# bristol_longshot.net
KiCad netlist of a schematic drawn in EAGLE
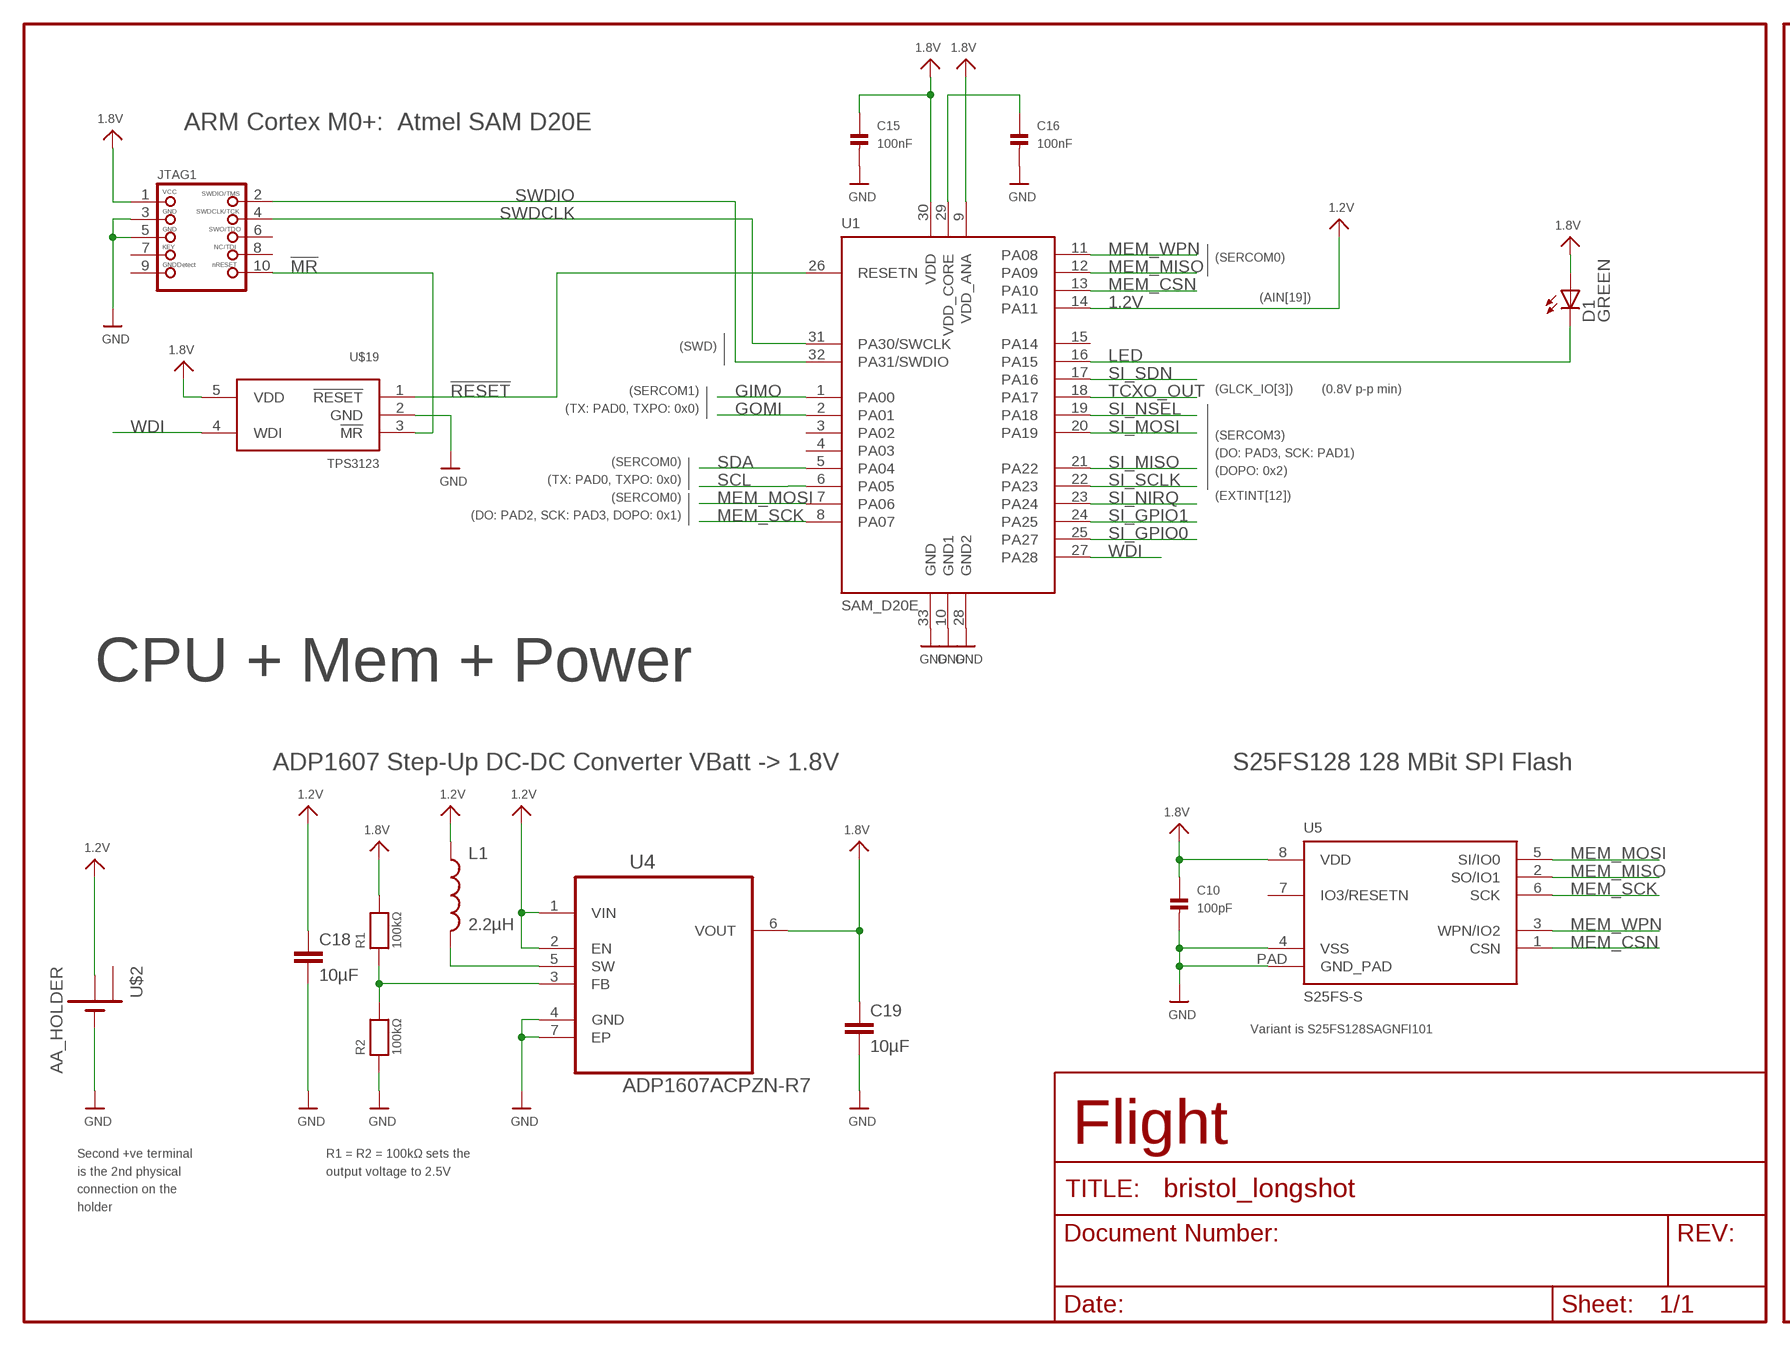
[diagram p0: schematic, sheet 1, part 1 of 2]
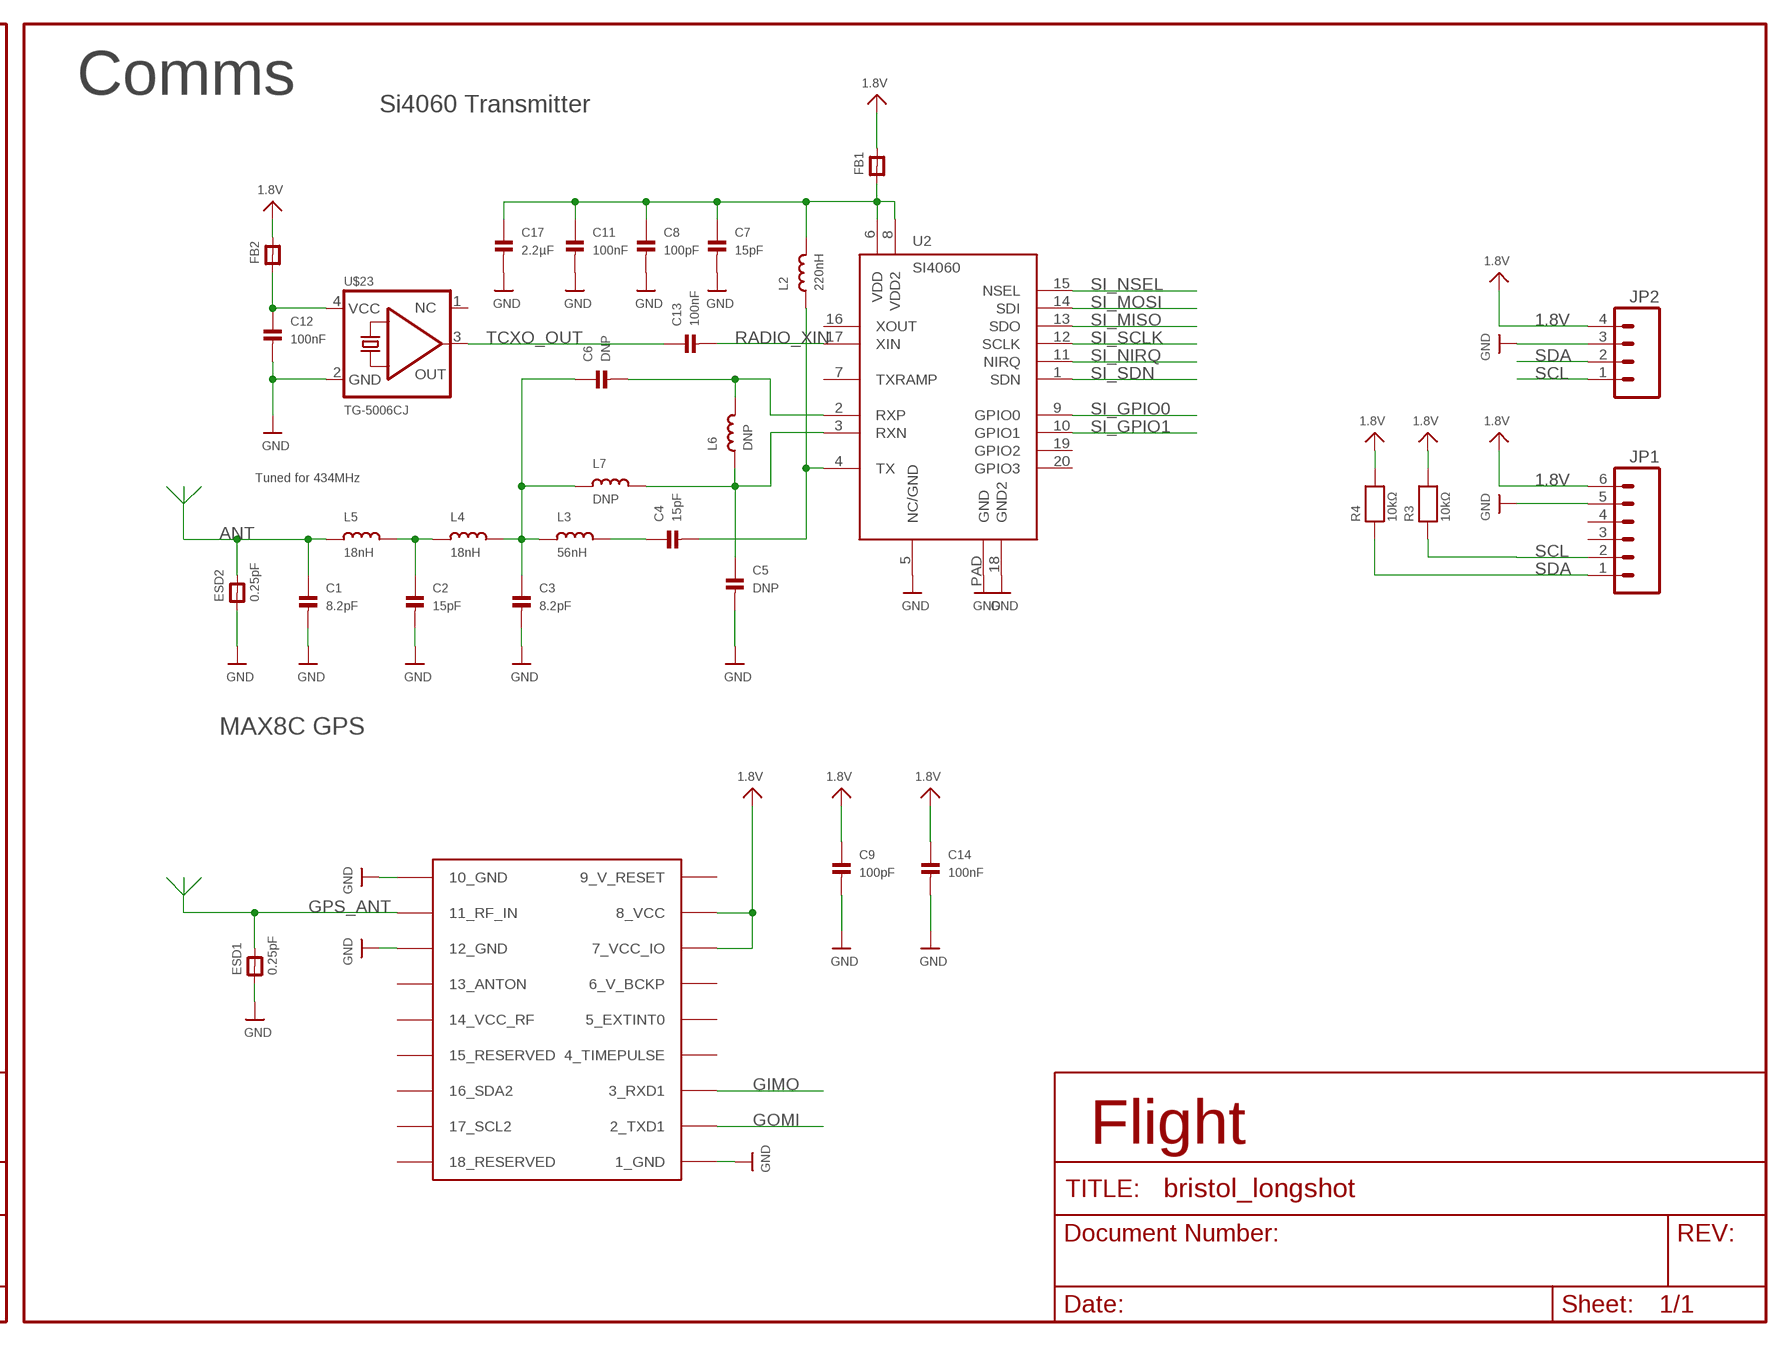
[diagram p1: schematic, sheet 1, part 2 of 2]

(export (version "E")
  (design (tool "Eeschema 10.0.6"))
  (components
    (comp (ref "C1")
      (value "8.2pF")
      (footprint "eagle-import:_0402")
      (libsource (lib "eagle-import") (part "CAP_CERAMIC_0402"))
    )
    (comp (ref "C2")
      (value "15pF")
      (footprint "eagle-import:_0402")
      (libsource (lib "eagle-import") (part "CAP_CERAMIC_0402"))
    )
    (comp (ref "C3")
      (value "8.2pF")
      (footprint "eagle-import:_0402")
      (libsource (lib "eagle-import") (part "CAP_CERAMIC_0402"))
    )
    (comp (ref "C4")
      (value "15pF")
      (footprint "eagle-import:_0402")
      (libsource (lib "eagle-import") (part "CAP_CERAMIC_0402"))
    )
    (comp (ref "C5")
      (value "DNP")
      (footprint "eagle-import:_0402")
      (libsource (lib "eagle-import") (part "CAP_CERAMIC_0402"))
    )
    (comp (ref "C6")
      (value "DNP")
      (footprint "eagle-import:_0402")
      (libsource (lib "eagle-import") (part "CAP_CERAMIC_0402"))
    )
    (comp (ref "C7")
      (value "15pF")
      (footprint "eagle-import:_0402")
      (libsource (lib "eagle-import") (part "CAP_CERAMIC_0402"))
    )
    (comp (ref "C8")
      (value "100pF")
      (footprint "eagle-import:_0402")
      (libsource (lib "eagle-import") (part "CAP_CERAMIC_0402"))
    )
    (comp (ref "C9")
      (value "100pF")
      (footprint "eagle-import:_0402")
      (libsource (lib "eagle-import") (part "CAP_CERAMIC_0402"))
    )
    (comp (ref "C10")
      (value "100pF")
      (footprint "eagle-import:_0402")
      (libsource (lib "eagle-import") (part "CAP_CERAMIC_0402"))
    )
    (comp (ref "C11")
      (value "100nF")
      (footprint "eagle-import:_0402")
      (libsource (lib "eagle-import") (part "CAP_CERAMIC_0402"))
    )
    (comp (ref "C12")
      (value "100nF")
      (footprint "eagle-import:_0402")
      (libsource (lib "eagle-import") (part "CAP_CERAMIC_0402"))
    )
    (comp (ref "C13")
      (value "100nF")
      (footprint "eagle-import:_0402")
      (libsource (lib "eagle-import") (part "CAP_CERAMIC_0402"))
    )
    (comp (ref "C14")
      (value "100nF")
      (footprint "eagle-import:_0402")
      (libsource (lib "eagle-import") (part "CAP_CERAMIC_0402"))
    )
    (comp (ref "C15")
      (value "100nF")
      (footprint "eagle-import:_0402")
      (libsource (lib "eagle-import") (part "CAP_CERAMIC_0402"))
    )
    (comp (ref "C16")
      (value "100nF")
      (footprint "eagle-import:_0402")
      (libsource (lib "eagle-import") (part "CAP_CERAMIC_0402"))
    )
    (comp (ref "C17")
      (value "2.2µF")
      (footprint "eagle-import:_0402")
      (libsource (lib "eagle-import") (part "CAP_CERAMIC_0402"))
    )
    (comp (ref "C18")
      (value "10µF")
      (footprint "eagle-import:C0603K")
      (libsource (lib "eagle-import") (part "C-EUC0603K"))
    )
    (comp (ref "C19")
      (value "10µF")
      (footprint "eagle-import:C0603K")
      (libsource (lib "eagle-import") (part "C-EUC0603K"))
    )
    (comp (ref "D1")
      (value "GREEN")
      (footprint "eagle-import:CHIPLED_0603")
      (libsource (lib "eagle-import") (part "LEDCHIPLED_0603"))
    )
    (comp (ref "ESD1")
      (value "0.25pF")
      (footprint "eagle-import:_0603MP")
      (libsource (lib "eagle-import") (part "FERRITE_0603MP"))
    )
    (comp (ref "ESD2")
      (value "0.25pF")
      (footprint "eagle-import:_0603MP")
      (libsource (lib "eagle-import") (part "FERRITE_0603MP"))
    )
    (comp (ref "FB1")
      (value "FERRITE_0402")
      (footprint "eagle-import:_0402")
      (libsource (lib "eagle-import") (part "FERRITE_0402"))
    )
    (comp (ref "FB2")
      (value "FERRITE_0402")
      (footprint "eagle-import:_0402")
      (libsource (lib "eagle-import") (part "FERRITE_0402"))
    )
    (comp (ref "JP1")
      (value "M06LOCK")
      (footprint "eagle-import:1X06_LOCK")
      (libsource (lib "eagle-import") (part "M06LOCK"))
    )
    (comp (ref "JP2")
      (value "M04LOCK")
      (footprint "eagle-import:1X04_LOCK")
      (libsource (lib "eagle-import") (part "M04LOCK"))
    )
    (comp (ref "JTAG1")
      (value "JTAG-CORTEXM3SMT")
      (footprint "eagle-import:2X05_1.27MM_SMT")
      (libsource (lib "eagle-import") (part "JTAG-CORTEXM3SMT"))
    )
    (comp (ref "L1")
      (value "2.2µH")
      (footprint "eagle-import:1007")
      (libsource (lib "eagle-import") (part "INDUCTOR1007"))
    )
    (comp (ref "L2")
      (value "220nH")
      (footprint "eagle-import:_0402")
      (libsource (lib "eagle-import") (part "INDUCTOR_0402"))
    )
    (comp (ref "L3")
      (value "56nH")
      (footprint "eagle-import:_0402")
      (libsource (lib "eagle-import") (part "INDUCTOR_0402"))
    )
    (comp (ref "L4")
      (value "18nH")
      (footprint "eagle-import:_0402")
      (libsource (lib "eagle-import") (part "INDUCTOR_0402"))
    )
    (comp (ref "L5")
      (value "18nH")
      (footprint "eagle-import:_0402")
      (libsource (lib "eagle-import") (part "INDUCTOR_0402"))
    )
    (comp (ref "L6")
      (value "DNP")
      (footprint "eagle-import:_0402")
      (libsource (lib "eagle-import") (part "INDUCTOR_0402"))
    )
    (comp (ref "L7")
      (value "DNP")
      (footprint "eagle-import:_0402")
      (libsource (lib "eagle-import") (part "INDUCTOR_0402"))
    )
    (comp (ref "R1")
      (value "100kΩ")
      (footprint "eagle-import:_0402")
      (libsource (lib "eagle-import") (part "RESISTOR_0402"))
    )
    (comp (ref "R2")
      (value "100kΩ")
      (footprint "eagle-import:_0402")
      (libsource (lib "eagle-import") (part "RESISTOR_0402"))
    )
    (comp (ref "R3")
      (value "10kΩ")
      (footprint "eagle-import:_0402")
      (libsource (lib "eagle-import") (part "RESISTOR_0402"))
    )
    (comp (ref "R4")
      (value "10kΩ")
      (footprint "eagle-import:_0402")
      (libsource (lib "eagle-import") (part "RESISTOR_0402"))
    )
    (comp (ref "U$2")
      (value "AA_HOLDER")
      (footprint "eagle-import:AA")
      (libsource (lib "eagle-import") (part "AA_HOLDER"))
    )
    (comp (ref "U$19")
      (value "TPS3123")
      (footprint "eagle-import:SOT23-5")
      (libsource (lib "eagle-import") (part "TPS3123"))
    )
    (comp (ref "U$23")
      (value "TG-5006CJ")
      (footprint "eagle-import:TC-5006CJ")
      (libsource (lib "eagle-import") (part "TG-5006CJ"))
    )
    (comp (ref "U$48")
      (value "UBLOX_MAX")
      (footprint "eagle-import:UBLOX_MAX")
      (libsource (lib "eagle-import") (part "UBLOX_MAX"))
    )
    (comp (ref "U1")
      (value "SAM_D20E")
      (footprint "eagle-import:QFN32_5MM")
      (libsource (lib "eagle-import") (part "SAM_D20E"))
    )
    (comp (ref "U2")
      (value "SI4060")
      (footprint "eagle-import:QFN20")
      (libsource (lib "eagle-import") (part "SI4060"))
    )
    (comp (ref "U4")
      (value "ADP1607ACPZN-R7")
      (footprint "eagle-import:DFN200X200X60-7N")
      (libsource (lib "eagle-import") (part "ADP1607ACPZN-R7"))
    )
    (comp (ref "U5")
      (value "S25FS-S")
      (footprint "eagle-import:WSON8")
      (libsource (lib "eagle-import") (part "S25FS-S"))
    )
  )
  (nets
    (net (code "1") (name "/+2") (class "Default")
      (node (ref "U$2") (pin "+1") (pinfunction "+2_+1") (pintype "power_in"))
    )
    (net (code "2") (name "/9_V_RESET") (class "Default")
      (node (ref "U$48") (pin "9_V_RESET") (pinfunction "9_V_RESET_9_V_RESET") (pintype "power_in"))
    )
    (net (code "3") (name "/ANT") (class "Default")
      (node (ref "C1") (pin "1") (pinfunction "P$1_1") (pintype "passive"))
      (node (ref "ESD2") (pin "2") (pinfunction "P$2_2") (pintype "passive"))
      (node (ref "L5") (pin "1") (pinfunction "1_1") (pintype "passive"))
    )
    (net (code "4") (name "/GIMO") (class "Default")
      (node (ref "U$48") (pin "3_RXD1") (pinfunction "3_RXD1_3_RXD1") (pintype "bidirectional"))
      (node (ref "U1") (pin "1") (pinfunction "PA00_1") (pintype "bidirectional"))
    )
    (net (code "5") (name "/GOMI") (class "Default")
      (node (ref "U$48") (pin "2_TXD1") (pinfunction "2_TXD1_2_TXD1") (pintype "bidirectional"))
      (node (ref "U1") (pin "2") (pinfunction "PA01_2") (pintype "bidirectional"))
    )
    (net (code "6") (name "/GPS_ANT") (class "Default")
      (node (ref "ESD1") (pin "2") (pinfunction "P$2_2") (pintype "passive"))
      (node (ref "U$48") (pin "11_RF_IN") (pinfunction "11_RF_IN_11_RF_IN") (pintype "bidirectional"))
    )
    (net (code "7") (name "/LED") (class "Default")
      (node (ref "D1") (pin "C") (pinfunction "C_C") (pintype "passive"))
      (node (ref "U1") (pin "16") (pinfunction "PA15_16") (pintype "bidirectional"))
    )
    (net (code "8") (name "/MEM_CSN") (class "Default")
      (node (ref "U1") (pin "13") (pinfunction "PA10_13") (pintype "bidirectional"))
      (node (ref "U5") (pin "1") (pinfunction "CSN_1") (pintype "input"))
    )
    (net (code "9") (name "/MEM_MISO") (class "Default")
      (node (ref "U1") (pin "12") (pinfunction "PA09_12") (pintype "bidirectional"))
      (node (ref "U5") (pin "2") (pinfunction "SO/IO1_2") (pintype "output"))
    )
    (net (code "10") (name "/MEM_MOSI") (class "Default")
      (node (ref "U1") (pin "7") (pinfunction "PA06_7") (pintype "bidirectional"))
      (node (ref "U5") (pin "5") (pinfunction "SI/IO0_5") (pintype "bidirectional"))
    )
    (net (code "11") (name "/MEM_SCK") (class "Default")
      (node (ref "U1") (pin "8") (pinfunction "PA07_8") (pintype "bidirectional"))
      (node (ref "U5") (pin "6") (pinfunction "SCK_6") (pintype "input"))
    )
    (net (code "12") (name "/MEM_WPN") (class "Default")
      (node (ref "U1") (pin "11") (pinfunction "PA08_11") (pintype "bidirectional"))
      (node (ref "U5") (pin "3") (pinfunction "WPN/IO2_3") (pintype "output"))
    )
    (net (code "13") (name "/RADIO_XIN") (class "Default")
      (node (ref "C13") (pin "2") (pinfunction "P$2_2") (pintype "passive"))
      (node (ref "U2") (pin "17") (pinfunction "XIN_17") (pintype "input"))
    )
    (net (code "14") (name "/SCL") (class "Default")
      (node (ref "JP1") (pin "2") (pinfunction "2_2") (pintype "passive"))
      (node (ref "JP2") (pin "1") (pinfunction "1_1") (pintype "passive"))
      (node (ref "R3") (pin "1") (pinfunction "1_1") (pintype "passive"))
      (node (ref "U1") (pin "6") (pinfunction "PA05_6") (pintype "bidirectional"))
    )
    (net (code "15") (name "/SDA") (class "Default")
      (node (ref "JP1") (pin "1") (pinfunction "1_1") (pintype "passive"))
      (node (ref "JP2") (pin "2") (pinfunction "2_2") (pintype "passive"))
      (node (ref "R4") (pin "1") (pinfunction "1_1") (pintype "passive"))
      (node (ref "U1") (pin "5") (pinfunction "PA04_5") (pintype "bidirectional"))
    )
    (net (code "16") (name "/SI_GPIO0") (class "Default")
      (node (ref "U1") (pin "25") (pinfunction "PA27_25") (pintype "bidirectional"))
      (node (ref "U2") (pin "9") (pinfunction "GPIO0_9") (pintype "bidirectional"))
    )
    (net (code "17") (name "/SI_GPIO1") (class "Default")
      (node (ref "U1") (pin "24") (pinfunction "PA25_24") (pintype "bidirectional"))
      (node (ref "U2") (pin "10") (pinfunction "GPIO1_10") (pintype "bidirectional"))
    )
    (net (code "18") (name "/SI_MISO") (class "Default")
      (node (ref "U1") (pin "21") (pinfunction "PA22_21") (pintype "bidirectional"))
      (node (ref "U2") (pin "13") (pinfunction "SDO_13") (pintype "output"))
    )
    (net (code "19") (name "/SI_MOSI") (class "Default")
      (node (ref "U1") (pin "20") (pinfunction "PA19_20") (pintype "bidirectional"))
      (node (ref "U2") (pin "14") (pinfunction "SDI_14") (pintype "bidirectional"))
    )
    (net (code "20") (name "/SI_NIRQ") (class "Default")
      (node (ref "U1") (pin "23") (pinfunction "PA24_23") (pintype "bidirectional"))
      (node (ref "U2") (pin "11") (pinfunction "NIRQ_11") (pintype "output"))
    )
    (net (code "21") (name "/SI_NSEL") (class "Default")
      (node (ref "U1") (pin "19") (pinfunction "PA18_19") (pintype "bidirectional"))
      (node (ref "U2") (pin "15") (pinfunction "NSEL_15") (pintype "input"))
    )
    (net (code "22") (name "/SI_SCLK") (class "Default")
      (node (ref "U1") (pin "22") (pinfunction "PA23_22") (pintype "bidirectional"))
      (node (ref "U2") (pin "12") (pinfunction "SCLK_12") (pintype "input"))
    )
    (net (code "23") (name "/SI_SDN") (class "Default")
      (node (ref "U1") (pin "17") (pinfunction "PA16_17") (pintype "bidirectional"))
      (node (ref "U2") (pin "1") (pinfunction "SDN_1") (pintype "input"))
    )
    (net (code "24") (name "/SWDCLK") (class "Default")
      (node (ref "JTAG1") (pin "4") (pinfunction "4_4") (pintype "passive"))
      (node (ref "U1") (pin "31") (pinfunction "PA30/SWCLK_31") (pintype "bidirectional"))
    )
    (net (code "25") (name "/SWDIO") (class "Default")
      (node (ref "JTAG1") (pin "2") (pinfunction "2_2") (pintype "passive"))
      (node (ref "U1") (pin "32") (pinfunction "PA31/SWDIO_32") (pintype "bidirectional"))
    )
    (net (code "26") (name "/TCXO_OUT") (class "Default")
      (node (ref "C13") (pin "1") (pinfunction "P$1_1") (pintype "passive"))
      (node (ref "U$23") (pin "3") (pinfunction "OUT_3") (pintype "output"))
      (node (ref "U1") (pin "18") (pinfunction "PA17_18") (pintype "bidirectional"))
    )
    (net (code "27") (name "/WDI") (class "Default")
      (node (ref "U$19") (pin "4") (pinfunction "WDI_4") (pintype "bidirectional"))
      (node (ref "U1") (pin "27") (pinfunction "PA28_27") (pintype "bidirectional"))
    )
    (net (code "28") (name "/~{MR}") (class "Default")
      (node (ref "JTAG1") (pin "10") (pinfunction "10_10") (pintype "passive"))
      (node (ref "U$19") (pin "3") (pinfunction "~{MR}_3") (pintype "bidirectional"))
    )
    (net (code "29") (name "/~{RESET}") (class "Default")
      (node (ref "U$19") (pin "1") (pinfunction "~{RESET}_1") (pintype "bidirectional"))
      (node (ref "U1") (pin "26") (pinfunction "RESETN_26") (pintype "input"))
    )
    (net (code "30") (name "1.2V") (class "Default")
      (node (ref "C18") (pin "1") (pinfunction "1_1") (pintype "passive"))
      (node (ref "L1") (pin "1") (pinfunction "1_1") (pintype "passive"))
      (node (ref "U$2") (pin "+2") (pinfunction "+_+2") (pintype "power_in"))
      (node (ref "U1") (pin "14") (pinfunction "PA11_14") (pintype "bidirectional"))
      (node (ref "U4") (pin "1") (pinfunction "VIN_1") (pintype "power_in"))
      (node (ref "U4") (pin "2") (pinfunction "EN_2") (pintype "input"))
    )
    (net (code "31") (name "1.8V") (class "Default")
      (node (ref "C10") (pin "1") (pinfunction "P$1_1") (pintype "passive"))
      (node (ref "C14") (pin "1") (pinfunction "P$1_1") (pintype "passive"))
      (node (ref "C15") (pin "1") (pinfunction "P$1_1") (pintype "passive"))
      (node (ref "C19") (pin "1") (pinfunction "1_1") (pintype "passive"))
      (node (ref "C9") (pin "1") (pinfunction "P$1_1") (pintype "passive"))
      (node (ref "D1") (pin "A") (pinfunction "A_A") (pintype "passive"))
      (node (ref "FB1") (pin "2") (pinfunction "P$2_2") (pintype "passive"))
      (node (ref "FB2") (pin "2") (pinfunction "P$2_2") (pintype "passive"))
      (node (ref "JP1") (pin "6") (pinfunction "6_6") (pintype "passive"))
      (node (ref "JP2") (pin "4") (pinfunction "4_4") (pintype "passive"))
      (node (ref "JTAG1") (pin "1") (pinfunction "1_1") (pintype "passive"))
      (node (ref "R1") (pin "2") (pinfunction "2_2") (pintype "passive"))
      (node (ref "R3") (pin "2") (pinfunction "2_2") (pintype "passive"))
      (node (ref "R4") (pin "2") (pinfunction "2_2") (pintype "passive"))
      (node (ref "U$19") (pin "5") (pinfunction "VDD_5") (pintype "bidirectional"))
      (node (ref "U$48") (pin "7_VCC_IO") (pinfunction "7_VCC_IO_7_VCC_IO") (pintype "power_in"))
      (node (ref "U$48") (pin "8_VCC") (pinfunction "8_VCC_8_VCC") (pintype "power_in"))
      (node (ref "U1") (pin "30") (pinfunction "VDD_30") (pintype "power_in"))
      (node (ref "U1") (pin "9") (pinfunction "VDD_ANA_9") (pintype "power_in"))
      (node (ref "U4") (pin "6") (pinfunction "VOUT_6") (pintype "output"))
      (node (ref "U5") (pin "8") (pinfunction "VDD_8") (pintype "power_in"))
    )
    (net (code "32") (name "GND") (class "Default")
      (node (ref "C1") (pin "2") (pinfunction "P$2_2") (pintype "passive"))
      (node (ref "C10") (pin "2") (pinfunction "P$2_2") (pintype "passive"))
      (node (ref "C11") (pin "2") (pinfunction "P$2_2") (pintype "passive"))
      (node (ref "C12") (pin "2") (pinfunction "P$2_2") (pintype "passive"))
      (node (ref "C14") (pin "2") (pinfunction "P$2_2") (pintype "passive"))
      (node (ref "C15") (pin "2") (pinfunction "P$2_2") (pintype "passive"))
      (node (ref "C16") (pin "2") (pinfunction "P$2_2") (pintype "passive"))
      (node (ref "C17") (pin "2") (pinfunction "P$2_2") (pintype "passive"))
      (node (ref "C18") (pin "2") (pinfunction "2_2") (pintype "passive"))
      (node (ref "C19") (pin "2") (pinfunction "2_2") (pintype "passive"))
      (node (ref "C2") (pin "2") (pinfunction "P$2_2") (pintype "passive"))
      (node (ref "C3") (pin "2") (pinfunction "P$2_2") (pintype "passive"))
      (node (ref "C5") (pin "2") (pinfunction "P$2_2") (pintype "passive"))
      (node (ref "C7") (pin "2") (pinfunction "P$2_2") (pintype "passive"))
      (node (ref "C8") (pin "2") (pinfunction "P$2_2") (pintype "passive"))
      (node (ref "C9") (pin "2") (pinfunction "P$2_2") (pintype "passive"))
      (node (ref "ESD1") (pin "1") (pinfunction "P$1_1") (pintype "passive"))
      (node (ref "ESD2") (pin "1") (pinfunction "P$1_1") (pintype "passive"))
      (node (ref "JP1") (pin "5") (pinfunction "5_5") (pintype "passive"))
      (node (ref "JP2") (pin "3") (pinfunction "3_3") (pintype "passive"))
      (node (ref "JTAG1") (pin "3") (pinfunction "3_3") (pintype "passive"))
      (node (ref "JTAG1") (pin "5") (pinfunction "5_5") (pintype "passive"))
      (node (ref "R2") (pin "1") (pinfunction "1_1") (pintype "passive"))
      (node (ref "U$19") (pin "2") (pinfunction "GND_2") (pintype "bidirectional"))
      (node (ref "U$2") (pin "-1") (pinfunction "-_-1") (pintype "power_in"))
      (node (ref "U$2") (pin "-2") (pinfunction "-_-2") (pintype "power_in"))
      (node (ref "U$23") (pin "2") (pinfunction "GND_2") (pintype "power_in"))
      (node (ref "U$48") (pin "10_GND") (pinfunction "10_GND_10_GND") (pintype "power_in"))
      (node (ref "U$48") (pin "12_GND") (pinfunction "12_GND_12_GND") (pintype "power_in"))
      (node (ref "U$48") (pin "1_GND") (pinfunction "1_GND_1_GND") (pintype "power_in"))
      (node (ref "U1") (pin "10") (pinfunction "GND1_10") (pintype "power_in"))
      (node (ref "U1") (pin "28") (pinfunction "GND2_28") (pintype "power_in"))
      (node (ref "U1") (pin "33") (pinfunction "GND_33") (pintype "power_in"))
      (node (ref "U2") (pin "18") (pinfunction "GND2_18") (pintype "power_in"))
      (node (ref "U2") (pin "5") (pinfunction "NC/GND_5") (pintype "bidirectional"))
      (node (ref "U2") (pin "PAD") (pinfunction "GND_PAD") (pintype "power_in"))
      (node (ref "U4") (pin "4") (pinfunction "GND_4") (pintype "power_in"))
      (node (ref "U4") (pin "7") (pinfunction "EP_7") (pintype "passive"))
      (node (ref "U5") (pin "4") (pinfunction "VSS_4") (pintype "power_in"))
      (node (ref "U5") (pin "PAD") (pinfunction "GND_PAD_PAD") (pintype "power_in"))
    )
    (net (code "33") (name "Net-(C2-P$1)") (class "Default")
      (node (ref "C2") (pin "1") (pinfunction "P$1_1") (pintype "passive"))
      (node (ref "L4") (pin "1") (pinfunction "1_1") (pintype "passive"))
      (node (ref "L5") (pin "2") (pinfunction "2_2") (pintype "passive"))
    )
    (net (code "34") (name "Net-(C3-P$1)") (class "Default")
      (node (ref "C3") (pin "1") (pinfunction "P$1_1") (pintype "passive"))
      (node (ref "C6") (pin "1") (pinfunction "P$1_1") (pintype "passive"))
      (node (ref "L3") (pin "1") (pinfunction "1_1") (pintype "passive"))
      (node (ref "L4") (pin "2") (pinfunction "2_2") (pintype "passive"))
      (node (ref "L7") (pin "1") (pinfunction "1_1") (pintype "passive"))
    )
    (net (code "35") (name "Net-(C4-P$1)") (class "Default")
      (node (ref "C4") (pin "1") (pinfunction "P$1_1") (pintype "passive"))
      (node (ref "L3") (pin "2") (pinfunction "2_2") (pintype "passive"))
    )
    (net (code "36") (name "Net-(C4-P$2)") (class "Default")
      (node (ref "C4") (pin "2") (pinfunction "P$2_2") (pintype "passive"))
      (node (ref "L2") (pin "1") (pinfunction "1_1") (pintype "passive"))
      (node (ref "U2") (pin "4") (pinfunction "TX_4") (pintype "output"))
    )
    (net (code "37") (name "Net-(C5-P$1)") (class "Default")
      (node (ref "C5") (pin "1") (pinfunction "P$1_1") (pintype "passive"))
      (node (ref "L6") (pin "1") (pinfunction "1_1") (pintype "passive"))
      (node (ref "L7") (pin "2") (pinfunction "2_2") (pintype "passive"))
      (node (ref "U2") (pin "3") (pinfunction "RXN_3") (pintype "input"))
    )
    (net (code "38") (name "Net-(C6-P$2)") (class "Default")
      (node (ref "C6") (pin "2") (pinfunction "P$2_2") (pintype "passive"))
      (node (ref "L6") (pin "2") (pinfunction "2_2") (pintype "passive"))
      (node (ref "U2") (pin "2") (pinfunction "RXP_2") (pintype "input"))
    )
    (net (code "39") (name "Net-(C11-P$1)") (class "Default")
      (node (ref "C11") (pin "1") (pinfunction "P$1_1") (pintype "passive"))
      (node (ref "C17") (pin "1") (pinfunction "P$1_1") (pintype "passive"))
      (node (ref "C7") (pin "1") (pinfunction "P$1_1") (pintype "passive"))
      (node (ref "C8") (pin "1") (pinfunction "P$1_1") (pintype "passive"))
      (node (ref "FB1") (pin "1") (pinfunction "P$1_1") (pintype "passive"))
      (node (ref "L2") (pin "2") (pinfunction "2_2") (pintype "passive"))
      (node (ref "U2") (pin "6") (pinfunction "VDD_6") (pintype "power_in"))
      (node (ref "U2") (pin "8") (pinfunction "VDD2_8") (pintype "power_in"))
    )
    (net (code "40") (name "Net-(C12-P$1)") (class "Default")
      (node (ref "C12") (pin "1") (pinfunction "P$1_1") (pintype "passive"))
      (node (ref "FB2") (pin "1") (pinfunction "P$1_1") (pintype "passive"))
      (node (ref "U$23") (pin "4") (pinfunction "VCC_4") (pintype "power_in"))
    )
    (net (code "41") (name "Net-(C16-P$1)") (class "Default")
      (node (ref "C16") (pin "1") (pinfunction "P$1_1") (pintype "passive"))
      (node (ref "U1") (pin "29") (pinfunction "VDD_CORE_29") (pintype "power_in"))
    )
    (net (code "42") (name "Net-(U4-FB)") (class "Default")
      (node (ref "R1") (pin "1") (pinfunction "1_1") (pintype "passive"))
      (node (ref "R2") (pin "2") (pinfunction "2_2") (pintype "passive"))
      (node (ref "U4") (pin "3") (pinfunction "FB_3") (pintype "passive"))
    )
    (net (code "43") (name "Net-(U4-SW)") (class "Default")
      (node (ref "L1") (pin "2") (pinfunction "2_2") (pintype "passive"))
      (node (ref "U4") (pin "5") (pinfunction "SW_5") (pintype "passive"))
    )
    (net (code "44") (name "unconnected-(JP1-Pad3)") (class "Default")
      (node (ref "JP1") (pin "3") (pinfunction "3_3") (pintype "passive"))
    )
    (net (code "45") (name "unconnected-(JP1-Pad4)") (class "Default")
      (node (ref "JP1") (pin "4") (pinfunction "4_4") (pintype "passive"))
    )
    (net (code "46") (name "unconnected-(JTAG1-Pad6)") (class "Default")
      (node (ref "JTAG1") (pin "6") (pinfunction "6_6") (pintype "passive"))
    )
    (net (code "47") (name "unconnected-(JTAG1-Pad7)") (class "Default")
      (node (ref "JTAG1") (pin "7") (pinfunction "7_7") (pintype "passive"))
    )
    (net (code "48") (name "unconnected-(JTAG1-Pad8)") (class "Default")
      (node (ref "JTAG1") (pin "8") (pinfunction "8_8") (pintype "passive"))
    )
    (net (code "49") (name "unconnected-(JTAG1-Pad9)") (class "Default")
      (node (ref "JTAG1") (pin "9") (pinfunction "9_9") (pintype "passive"))
    )
    (net (code "50") (name "unconnected-(U$23-NC-Pad1)") (class "Default")
      (node (ref "U$23") (pin "1") (pinfunction "NC_1") (pintype "no_connect"))
    )
    (net (code "51") (name "unconnected-(U$48-Pad4_TIMEPULSE)") (class "Default")
      (node (ref "U$48") (pin "4_TIMEPULSE") (pinfunction "4_TIMEPULSE_4_TIMEPULSE") (pintype "bidirectional"))
    )
    (net (code "52") (name "unconnected-(U$48-Pad5_EXTINT0)") (class "Default")
      (node (ref "U$48") (pin "5_EXTINT0") (pinfunction "5_EXTINT0_5_EXTINT0") (pintype "bidirectional"))
    )
    (net (code "53") (name "unconnected-(U$48-Pad6_V_BCKP)") (class "Default")
      (node (ref "U$48") (pin "6_V_BCKP") (pinfunction "6_V_BCKP_6_V_BCKP") (pintype "bidirectional"))
    )
    (net (code "54") (name "unconnected-(U$48-Pad13_ANTON)") (class "Default")
      (node (ref "U$48") (pin "13_ANTON") (pinfunction "13_ANTON_13_ANTON") (pintype "bidirectional"))
    )
    (net (code "55") (name "unconnected-(U$48-Pad14_VCC_RF)") (class "Default")
      (node (ref "U$48") (pin "14_VCC_RF") (pinfunction "14_VCC_RF_14_VCC_RF") (pintype "bidirectional"))
    )
    (net (code "56") (name "unconnected-(U$48-Pad15_RESERVED)") (class "Default")
      (node (ref "U$48") (pin "15_RESERVED") (pinfunction "15_RESERVED_15_RESERVED") (pintype "bidirectional"))
    )
    (net (code "57") (name "unconnected-(U$48-Pad16_SDA2)") (class "Default")
      (node (ref "U$48") (pin "16_SDA2") (pinfunction "16_SDA2_16_SDA2") (pintype "bidirectional"))
    )
    (net (code "58") (name "unconnected-(U$48-Pad17_SCL2)") (class "Default")
      (node (ref "U$48") (pin "17_SCL2") (pinfunction "17_SCL2_17_SCL2") (pintype "bidirectional"))
    )
    (net (code "59") (name "unconnected-(U$48-Pad18_RESERVED)") (class "Default")
      (node (ref "U$48") (pin "18_RESERVED") (pinfunction "18_RESERVED_18_RESERVED") (pintype "bidirectional"))
    )
    (net (code "60") (name "unconnected-(U1-PA02-Pad3)") (class "Default")
      (node (ref "U1") (pin "3") (pinfunction "PA02_3") (pintype "bidirectional"))
    )
    (net (code "61") (name "unconnected-(U1-PA03-Pad4)") (class "Default")
      (node (ref "U1") (pin "4") (pinfunction "PA03_4") (pintype "bidirectional"))
    )
    (net (code "62") (name "unconnected-(U1-PA14-Pad15)") (class "Default")
      (node (ref "U1") (pin "15") (pinfunction "PA14_15") (pintype "bidirectional"))
    )
    (net (code "63") (name "unconnected-(U2-GPIO2-Pad19)") (class "Default")
      (node (ref "U2") (pin "19") (pinfunction "GPIO2_19") (pintype "bidirectional"))
    )
    (net (code "64") (name "unconnected-(U2-GPIO3-Pad20)") (class "Default")
      (node (ref "U2") (pin "20") (pinfunction "GPIO3_20") (pintype "bidirectional"))
    )
    (net (code "65") (name "unconnected-(U2-TXRAMP-Pad7)") (class "Default")
      (node (ref "U2") (pin "7") (pinfunction "TXRAMP_7") (pintype "bidirectional"))
    )
    (net (code "66") (name "unconnected-(U2-XOUT-Pad16)") (class "Default")
      (node (ref "U2") (pin "16") (pinfunction "XOUT_16") (pintype "output"))
    )
    (net (code "67") (name "unconnected-(U5-IO3{slash}RESETN-Pad7)") (class "Default")
      (node (ref "U5") (pin "7") (pinfunction "IO3/RESETN_7") (pintype "output"))
    )
  )
)
